# Front_right_lamp_v3.net
KiCad netlist of a schematic drawn in EAGLE
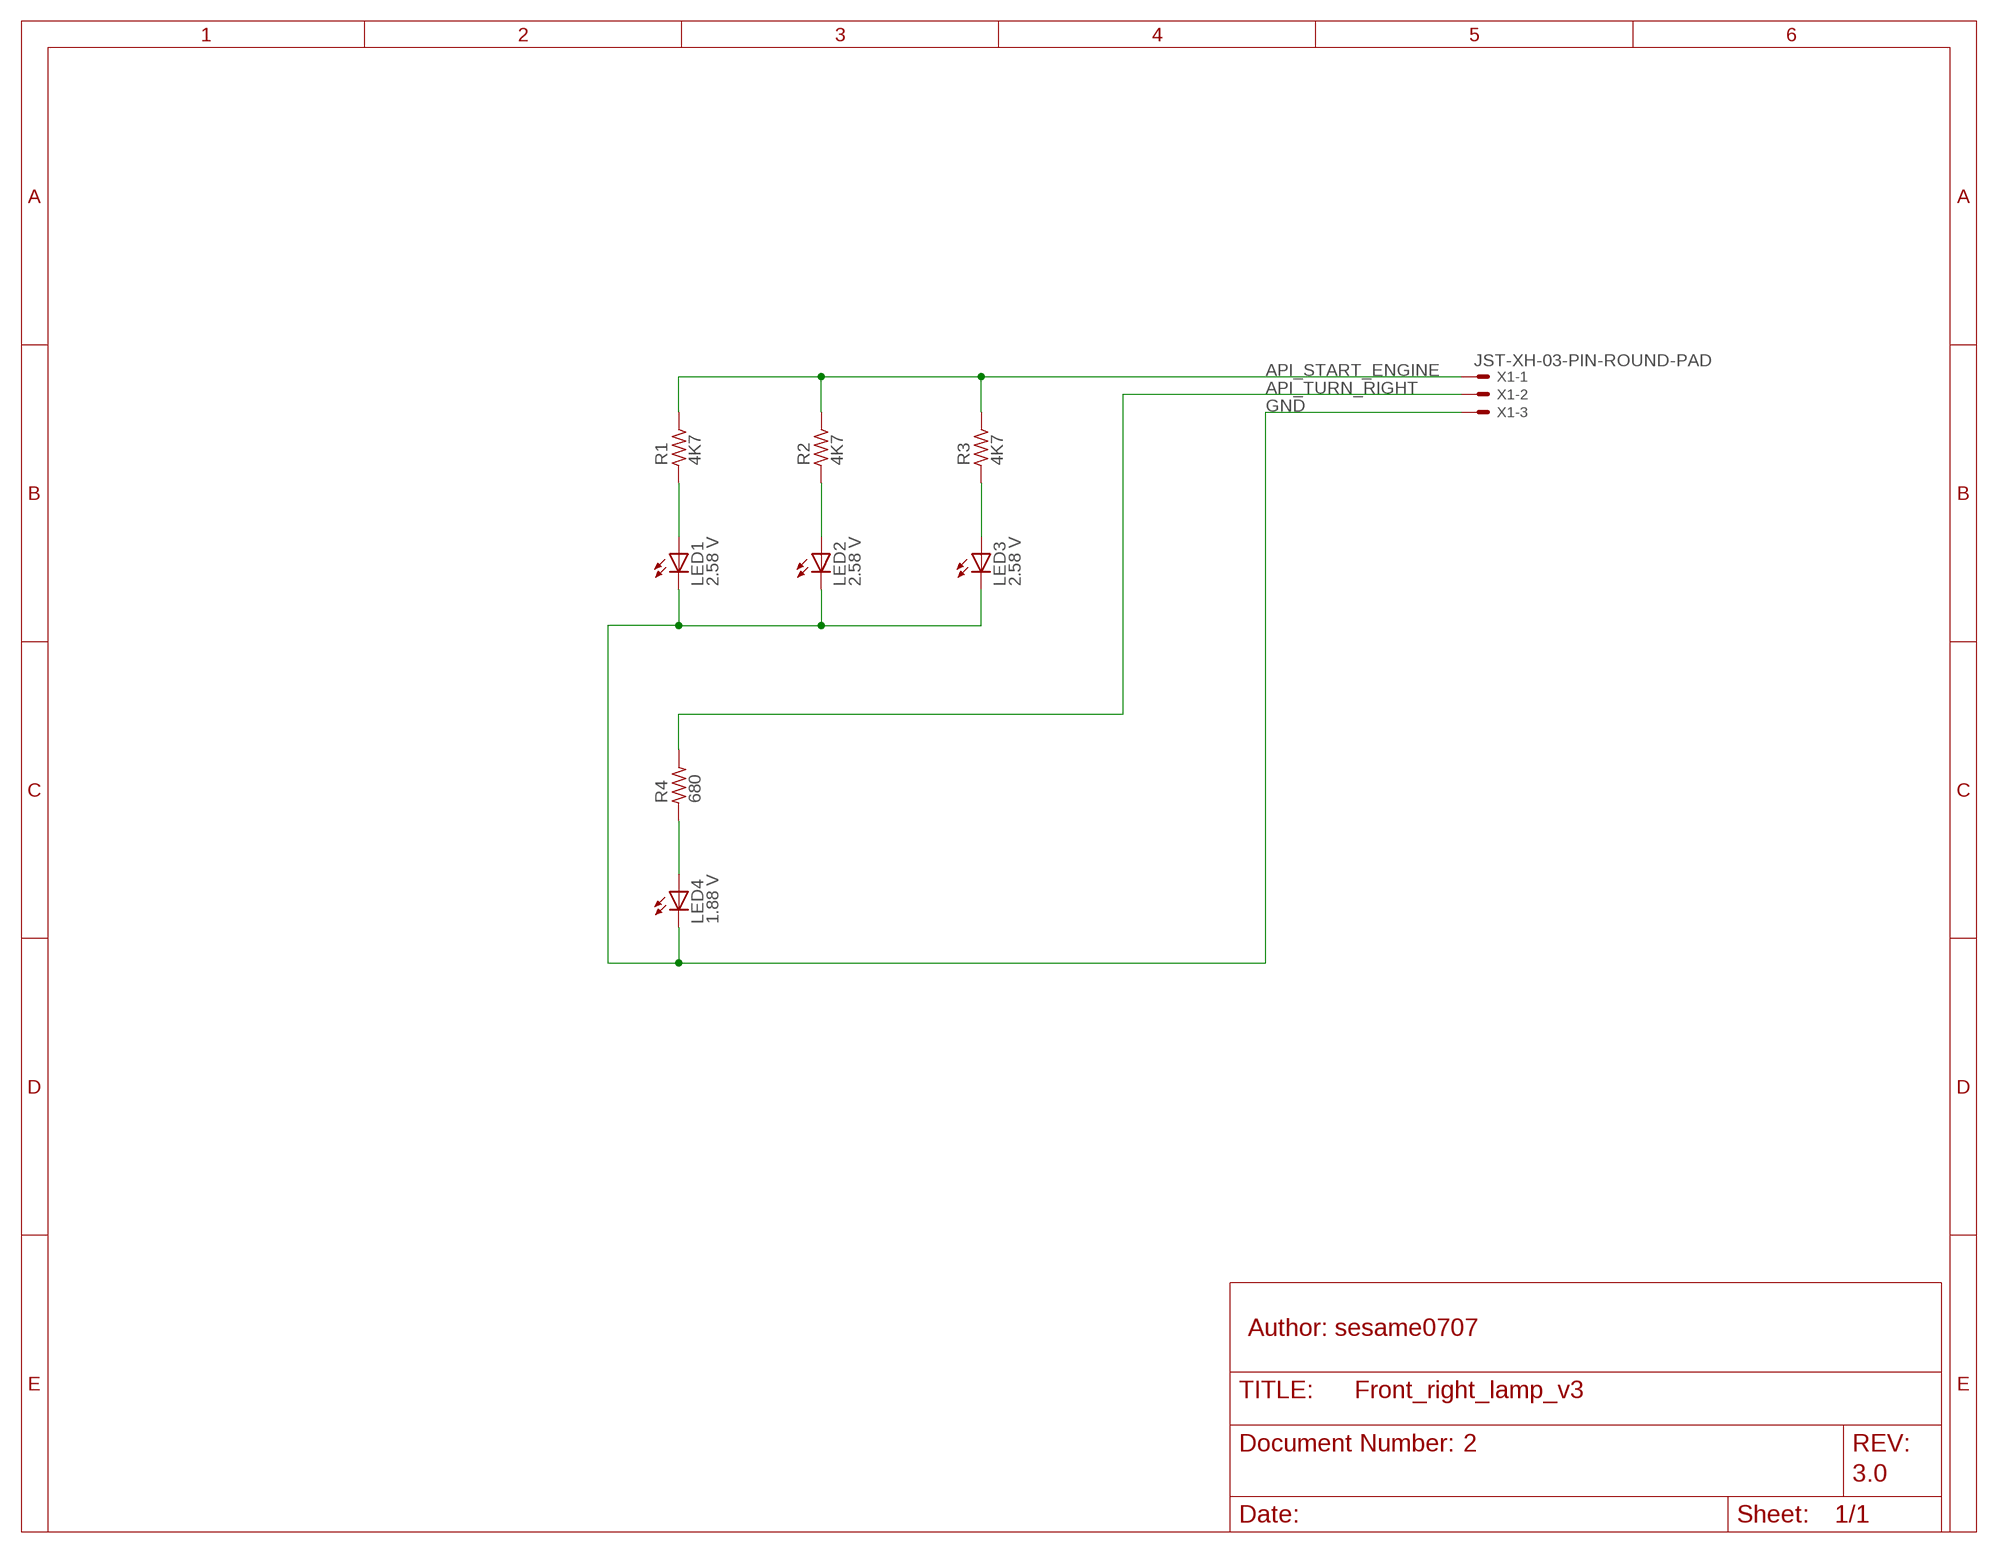
[diagram p0: schematic, sheet 1]

(export (version "E")
  (design (tool "Eeschema 10.0.6"))
  (components
    (comp (ref "LED1")
      (value "2.58 V")
      (footprint "eagle-import:LED5MM")
      (libsource (lib "eagle-import") (part "LED5MM"))
    )
    (comp (ref "LED2")
      (value "2.58 V")
      (footprint "eagle-import:LED5MM")
      (libsource (lib "eagle-import") (part "LED5MM"))
    )
    (comp (ref "LED3")
      (value "2.58 V")
      (footprint "eagle-import:LED5MM")
      (libsource (lib "eagle-import") (part "LED5MM"))
    )
    (comp (ref "LED4")
      (value "1.88 V")
      (footprint "eagle-import:LED5MM")
      (libsource (lib "eagle-import") (part "LED5MM"))
    )
    (comp (ref "R1")
      (value "4K7")
      (footprint "eagle-import:R0805")
      (libsource (lib "eagle-import") (part "R_0805"))
    )
    (comp (ref "R2")
      (value "4K7")
      (footprint "eagle-import:R0805")
      (libsource (lib "eagle-import") (part "R_0805"))
    )
    (comp (ref "R3")
      (value "4K7")
      (footprint "eagle-import:R0805")
      (libsource (lib "eagle-import") (part "R_0805"))
    )
    (comp (ref "R4")
      (value "680")
      (footprint "eagle-import:R0805")
      (libsource (lib "eagle-import") (part "R_0805"))
    )
    (comp (ref "X1")
      (value "JST-XH-03-PIN-ROUND-PAD")
      (footprint "eagle-import:JST-XH-03-PACKAGE-ROUND-PAD")
      (libsource (lib "eagle-import") (part "JST-XH-03-PIN-ROUND-PAD"))
    )
  )
  (nets
    (net (code "1") (name "/API_START_ENGINE") (class "Default")
      (node (ref "R1") (pin "2") (pinfunction "2_2") (pintype "passive"))
      (node (ref "R2") (pin "2") (pinfunction "2_2") (pintype "passive"))
      (node (ref "R3") (pin "2") (pinfunction "2_2") (pintype "passive"))
      (node (ref "X1") (pin "1") (pinfunction "S_1") (pintype "passive"))
    )
    (net (code "2") (name "/API_TURN_RIGHT") (class "Default")
      (node (ref "R4") (pin "2") (pinfunction "2_2") (pintype "passive"))
      (node (ref "X1") (pin "2") (pinfunction "S_2") (pintype "passive"))
    )
    (net (code "3") (name "/GND") (class "Default")
      (node (ref "LED1") (pin "K") (pinfunction "C_K") (pintype "passive"))
      (node (ref "LED2") (pin "K") (pinfunction "C_K") (pintype "passive"))
      (node (ref "LED3") (pin "K") (pinfunction "C_K") (pintype "passive"))
      (node (ref "LED4") (pin "K") (pinfunction "C_K") (pintype "passive"))
      (node (ref "X1") (pin "3") (pinfunction "S_3") (pintype "passive"))
    )
    (net (code "4") (name "Net-(LED1-PadA)") (class "Default")
      (node (ref "LED1") (pin "A") (pinfunction "A_A") (pintype "passive"))
      (node (ref "R1") (pin "1") (pinfunction "1_1") (pintype "passive"))
    )
    (net (code "5") (name "Net-(LED2-PadA)") (class "Default")
      (node (ref "LED2") (pin "A") (pinfunction "A_A") (pintype "passive"))
      (node (ref "R2") (pin "1") (pinfunction "1_1") (pintype "passive"))
    )
    (net (code "6") (name "Net-(LED3-PadA)") (class "Default")
      (node (ref "LED3") (pin "A") (pinfunction "A_A") (pintype "passive"))
      (node (ref "R3") (pin "1") (pinfunction "1_1") (pintype "passive"))
    )
    (net (code "7") (name "Net-(LED4-PadA)") (class "Default")
      (node (ref "LED4") (pin "A") (pinfunction "A_A") (pintype "passive"))
      (node (ref "R4") (pin "1") (pinfunction "1_1") (pintype "passive"))
    )
  )
)
